# ToolDoorController.net
KiCad netlist of a schematic drawn in Altium Designer
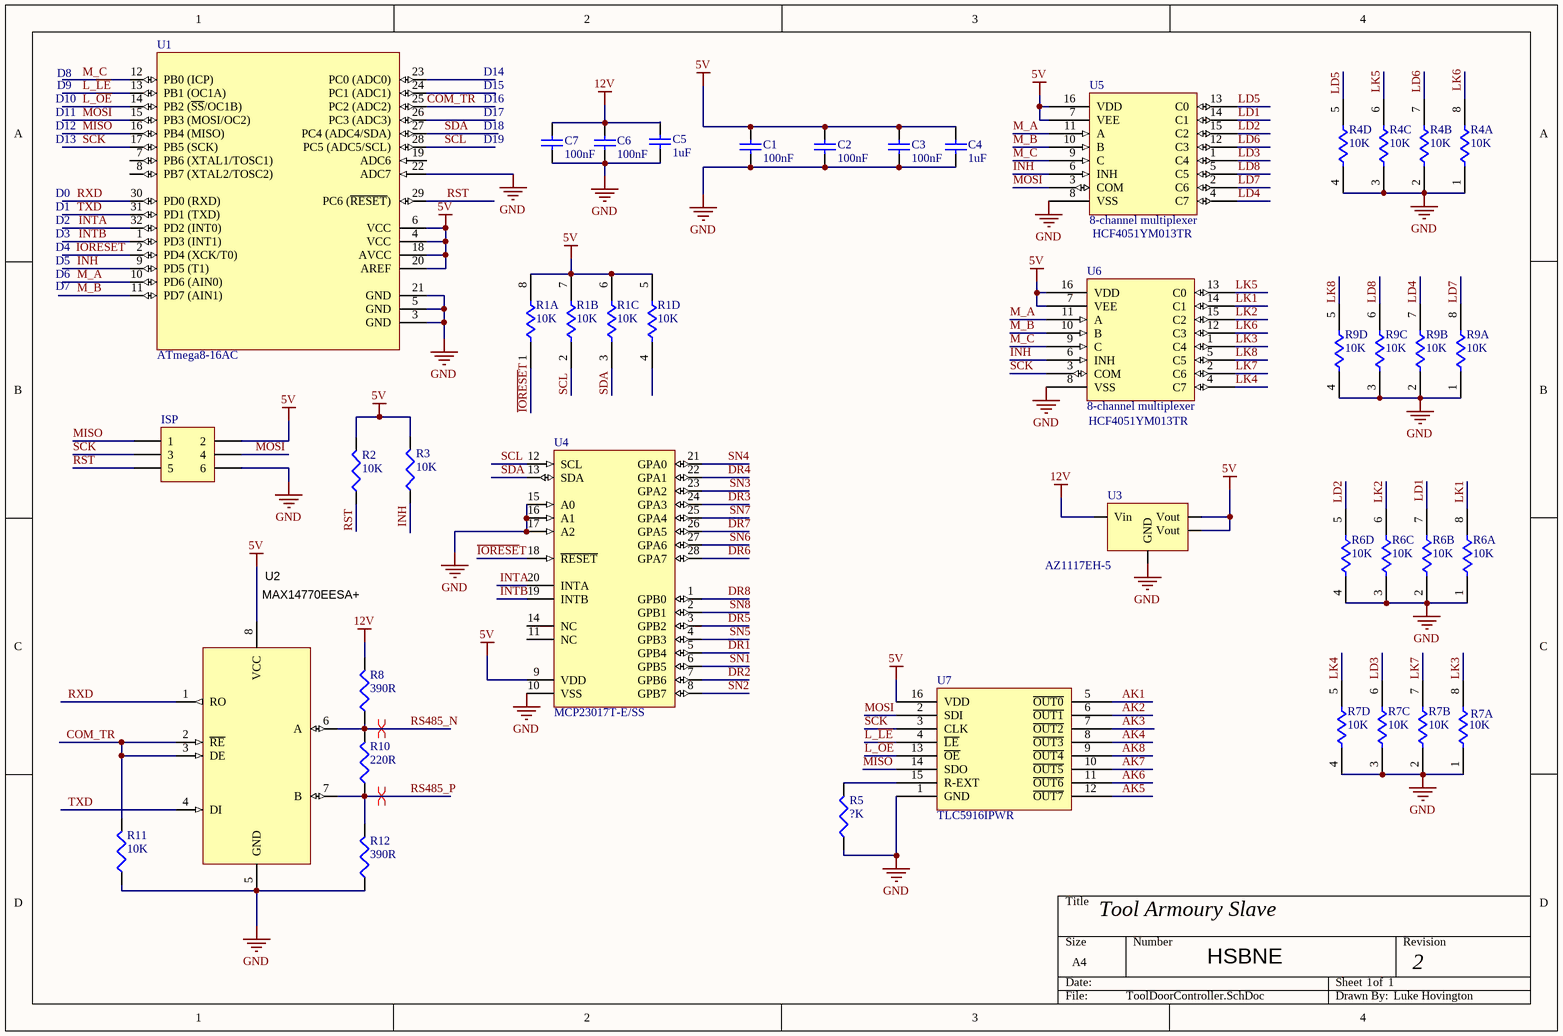
[diagram p0: ToolDoorController.SchDoc]

(export (version "E")
  (design (tool "Eeschema 10.0.6"))
  (components
    (comp (ref "C1")
      (value "100nF")
      (footprint "C1206")
      (description "Capacitor (Semiconductor SIM Model)")
      (fields (field (name "PUBLISHER") "Altium Limited"))
      (libsource (lib "ToolDoorController") (part "Cap 100nF"))
    )
    (comp (ref "C2")
      (value "100nF")
      (footprint "C1206")
      (description "Capacitor (Semiconductor SIM Model)")
      (fields (field (name "PUBLISHER") "Altium Limited"))
      (libsource (lib "ToolDoorController") (part "Cap 100nF"))
    )
    (comp (ref "C3")
      (value "100nF")
      (footprint "C1206")
      (description "Capacitor (Semiconductor SIM Model)")
      (fields (field (name "PUBLISHER") "Altium Limited"))
      (libsource (lib "ToolDoorController") (part "Cap 100nF"))
    )
    (comp (ref "C4")
      (value "1uF")
      (footprint "C1206")
      (description "Capacitor (Semiconductor SIM Model)")
      (fields (field (name "PUBLISHER") "Altium Limited"))
      (libsource (lib "ToolDoorController") (part "Cap 1uF"))
    )
    (comp (ref "C5")
      (value "1uF")
      (footprint "C1206")
      (description "Capacitor (Semiconductor SIM Model)")
      (fields (field (name "PUBLISHER") "Altium Limited"))
      (libsource (lib "ToolDoorController") (part "Cap 1uF"))
    )
    (comp (ref "C6")
      (value "100nF")
      (footprint "C1206")
      (description "Capacitor (Semiconductor SIM Model)")
      (fields (field (name "PUBLISHER") "Altium Limited"))
      (libsource (lib "ToolDoorController") (part "Cap 100nF"))
    )
    (comp (ref "C7")
      (value "100nF")
      (footprint "C1206")
      (description "Capacitor (Semiconductor SIM Model)")
      (fields (field (name "PUBLISHER") "Altium Limited"))
      (libsource (lib "ToolDoorController") (part "Cap 100nF"))
    )
    (comp (ref "ISP")
      (value "ISP")
      (footprint "HDR2X3")
      (description "Header, 3-Pin, Dual row")
      (fields (field (name "PUBLISHER") "Altium Limited"))
      (libsource (lib "ToolDoorController") (part "Header 3X2"))
    )
    (comp (ref "R1")
      (value "10K")
      (footprint "SO8_S")
      (description "Isolated Resistor Network - Parts")
      (fields (field (name "PUBLISHER") "Altium Limited"))
      (libsource (lib "ToolDoorController") (part "Resistor Pack"))
    )
    (comp (ref "R2")
      (value "10K")
      (footprint "C1206")
      (description "Resistor")
      (fields (field (name "PUBLISHER") "Altium Limited"))
      (libsource (lib "ToolDoorController") (part "Resistor-10K"))
    )
    (comp (ref "R3")
      (value "10K")
      (footprint "C1206")
      (description "Resistor")
      (fields (field (name "PUBLISHER") "Altium Limited"))
      (libsource (lib "ToolDoorController") (part "Resistor-10K"))
    )
    (comp (ref "R4")
      (value "10K")
      (footprint "SO8_S")
      (description "Isolated Resistor Network - Parts")
      (fields (field (name "PUBLISHER") "Altium Limited"))
      (libsource (lib "ToolDoorController") (part "Resistor Pack"))
    )
    (comp (ref "R5")
      (value "?K")
      (footprint "C1206")
      (description "Resistor")
      (fields (field (name "PUBLISHER") "Altium Limited"))
      (libsource (lib "ToolDoorController") (part "Resistor-10K"))
    )
    (comp (ref "R6")
      (value "10K")
      (footprint "SO8_S")
      (description "Isolated Resistor Network - Parts")
      (fields (field (name "PUBLISHER") "Altium Limited"))
      (libsource (lib "ToolDoorController") (part "Resistor Pack"))
    )
    (comp (ref "R7")
      (value "10K")
      (footprint "SO8_S")
      (description "Isolated Resistor Network - Parts")
      (fields (field (name "PUBLISHER") "Altium Limited"))
      (libsource (lib "ToolDoorController") (part "Resistor Pack"))
    )
    (comp (ref "R8")
      (value "390R")
      (footprint "C1206")
      (description "Resistor")
      (fields (field (name "PUBLISHER") "Altium Limited"))
      (libsource (lib "ToolDoorController") (part "Resistor-390R"))
    )
    (comp (ref "R9")
      (value "10K")
      (footprint "SO8_S")
      (description "Isolated Resistor Network - Parts")
      (fields (field (name "PUBLISHER") "Altium Limited"))
      (libsource (lib "ToolDoorController") (part "Resistor Pack"))
    )
    (comp (ref "R10")
      (value "220R")
      (footprint "C1206")
      (description "Resistor")
      (fields (field (name "PUBLISHER") "Altium Limited"))
      (libsource (lib "ToolDoorController") (part "Resistor-220R"))
    )
    (comp (ref "R11")
      (value "10K")
      (footprint "C1206")
      (description "Resistor")
      (fields (field (name "PUBLISHER") "Altium Limited"))
      (libsource (lib "ToolDoorController") (part "Resistor-10K"))
    )
    (comp (ref "R12")
      (value "390R")
      (footprint "C1206")
      (description "Resistor")
      (fields (field (name "PUBLISHER") "Altium Limited"))
      (libsource (lib "ToolDoorController") (part "Resistor-390R"))
    )
    (comp (ref "U1")
      (value "ATmega8-16AC")
      (footprint "32A_N")
      (description "8-Bit AVR Microcontroller with 8K Bytes of In-System Programmable Flash Memory")
      (fields (field (name "PUBLISHER") "Altium Limited"))
      (libsource (lib "ToolDoorController") (part "ATmega8-16AC"))
    )
    (comp (ref "U2")
      (value "MAX14770EESA+")
      (footprint "8S1_L")
      (description "TXRX PROFIBUS RS-485 8-SOIC")
      (libsource (lib "ToolDoorController") (part "MAX14770EESA+"))
    )
    (comp (ref "U3")
      (value "AZ1117EH-5")
      (footprint "SOT-223")
      (description "Reg 1A 5V OUT SIP VERT")
      (libsource (lib "ToolDoorController") (part "AZ1117EH"))
    )
    (comp (ref "U4")
      (value "MCP23017T-E/SS")
      (footprint "SSOP-SS28_N")
      (description "16-Bit I/O Expander with Serial Interface, 28-Pin SSOP, Extended Temperature, Tape and Reel")
      (libsource (lib "Altium Content Vault") (part "PR-BUSIC-MCP23017-28"))
    )
    (comp (ref "U5")
      (value "8-channel multiplexer")
      (footprint "16S1_M")
      (description "8-channel analog multiplexer/demultiplexer")
      (fields (field (name "MANUFACTURER PART NUMBER") "HCF4051YM013TR"))
      (libsource (lib "ToolDoorController") (part "8-channel multiplexer"))
    )
    (comp (ref "U6")
      (value "8-channel multiplexer")
      (footprint "16S1_M")
      (description "8-channel analog multiplexer/demultiplexer")
      (fields (field (name "MANUFACTURER PART NUMBER") "HCF4051YM013TR"))
      (libsource (lib "ToolDoorController") (part "8-channel multiplexer"))
    )
    (comp (ref "U7")
      (value "TLC5916IPWR")
      (footprint "DB016")
      (description "IC LED DRIVER LIN 120MA")
      (libsource (lib "ToolDoorController") (part "TLC5916IDR"))
    )
  )
  (nets
    (net (code "1") (name "/AK1") (class "Default")
      (node (ref "U7") (pin "5") (pinfunction "~{OUT0}_5") (pintype "power_in"))
    )
    (net (code "2") (name "/AK2") (class "Default")
      (node (ref "U7") (pin "6") (pinfunction "~{OUT1}_6") (pintype "power_in"))
    )
    (net (code "3") (name "/AK3") (class "Default")
      (node (ref "U7") (pin "7") (pinfunction "~{OUT2}_7") (pintype "power_in"))
    )
    (net (code "4") (name "/AK4") (class "Default")
      (node (ref "U7") (pin "8") (pinfunction "~{OUT3}_8") (pintype "power_in"))
    )
    (net (code "5") (name "/AK5") (class "Default")
      (node (ref "U7") (pin "12") (pinfunction "~{OUT7}_12") (pintype "power_in"))
    )
    (net (code "6") (name "/AK6") (class "Default")
      (node (ref "U7") (pin "11") (pinfunction "~{OUT6}_11") (pintype "power_in"))
    )
    (net (code "7") (name "/AK7") (class "Default")
      (node (ref "U7") (pin "10") (pinfunction "~{OUT5}_10") (pintype "power_in"))
    )
    (net (code "8") (name "/AK8") (class "Default")
      (node (ref "U7") (pin "9") (pinfunction "~{OUT4}_9") (pintype "power_in"))
    )
    (net (code "9") (name "/COM_TR") (class "Default")
      (node (ref "R11") (pin "2") (pinfunction "2_2") (pintype "passive"))
      (node (ref "U1") (pin "25") (pinfunction "PC2_(ADC2)_25") (pintype "bidirectional"))
      (node (ref "U2") (pin "2") (pinfunction "~{RE}_2") (pintype "input"))
      (node (ref "U2") (pin "3") (pinfunction "DE_3") (pintype "input"))
    )
    (net (code "10") (name "/DR1") (class "Default")
      (node (ref "U4") (pin "5") (pinfunction "GPB4_5") (pintype "bidirectional"))
    )
    (net (code "11") (name "/DR2") (class "Default")
      (node (ref "U4") (pin "7") (pinfunction "GPB6_7") (pintype "bidirectional"))
    )
    (net (code "12") (name "/DR3") (class "Default")
      (node (ref "U4") (pin "24") (pinfunction "GPA3_24") (pintype "bidirectional"))
    )
    (net (code "13") (name "/DR4") (class "Default")
      (node (ref "U4") (pin "22") (pinfunction "GPA1_22") (pintype "bidirectional"))
    )
    (net (code "14") (name "/DR5") (class "Default")
      (node (ref "U4") (pin "3") (pinfunction "GPB2_3") (pintype "bidirectional"))
    )
    (net (code "15") (name "/DR6") (class "Default")
      (node (ref "U4") (pin "28") (pinfunction "GPA7_28") (pintype "bidirectional"))
    )
    (net (code "16") (name "/DR7") (class "Default")
      (node (ref "U4") (pin "26") (pinfunction "GPA5_26") (pintype "bidirectional"))
    )
    (net (code "17") (name "/DR8") (class "Default")
      (node (ref "U4") (pin "1") (pinfunction "GPB0_1") (pintype "bidirectional"))
    )
    (net (code "18") (name "/INH") (class "Default")
      (node (ref "R3") (pin "1") (pinfunction "1_1") (pintype "passive"))
      (node (ref "U1") (pin "9") (pinfunction "PD5_(T1)_9") (pintype "bidirectional"))
      (node (ref "U5") (pin "6") (pinfunction "INH_6") (pintype "input"))
      (node (ref "U6") (pin "6") (pinfunction "INH_6") (pintype "input"))
    )
    (net (code "19") (name "/INTA") (class "Default")
      (node (ref "U1") (pin "32") (pinfunction "PD2_(INT0)_32") (pintype "bidirectional"))
      (node (ref "U4") (pin "20") (pinfunction "INTA_20") (pintype "open_collector"))
    )
    (net (code "20") (name "/INTB") (class "Default")
      (node (ref "U1") (pin "1") (pinfunction "PD3_(INT1)_1") (pintype "bidirectional"))
      (node (ref "U4") (pin "19") (pinfunction "INTB_19") (pintype "open_collector"))
    )
    (net (code "21") (name "/LD1") (class "Default")
      (node (ref "R6") (pin "7") (pinfunction "7_7") (pintype "passive"))
      (node (ref "U5") (pin "14") (pinfunction "C1_14") (pintype "bidirectional"))
    )
    (net (code "22") (name "/LD2") (class "Default")
      (node (ref "R6") (pin "5") (pinfunction "5_5") (pintype "passive"))
      (node (ref "U5") (pin "15") (pinfunction "C2_15") (pintype "bidirectional"))
    )
    (net (code "23") (name "/LD3") (class "Default")
      (node (ref "R7") (pin "6") (pinfunction "6_6") (pintype "passive"))
      (node (ref "U5") (pin "1") (pinfunction "C4_1") (pintype "bidirectional"))
    )
    (net (code "24") (name "/LD4") (class "Default")
      (node (ref "R9") (pin "7") (pinfunction "7_7") (pintype "passive"))
      (node (ref "U5") (pin "4") (pinfunction "C7_4") (pintype "bidirectional"))
    )
    (net (code "25") (name "/LD5") (class "Default")
      (node (ref "R4") (pin "5") (pinfunction "5_5") (pintype "passive"))
      (node (ref "U5") (pin "13") (pinfunction "C0_13") (pintype "bidirectional"))
    )
    (net (code "26") (name "/LD6") (class "Default")
      (node (ref "R4") (pin "7") (pinfunction "7_7") (pintype "passive"))
      (node (ref "U5") (pin "12") (pinfunction "C3_12") (pintype "bidirectional"))
    )
    (net (code "27") (name "/LD7") (class "Default")
      (node (ref "R9") (pin "8") (pinfunction "8_8") (pintype "passive"))
      (node (ref "U5") (pin "2") (pinfunction "C6_2") (pintype "bidirectional"))
    )
    (net (code "28") (name "/LD8") (class "Default")
      (node (ref "R9") (pin "6") (pinfunction "6_6") (pintype "passive"))
      (node (ref "U5") (pin "5") (pinfunction "C5_5") (pintype "bidirectional"))
    )
    (net (code "29") (name "/LK1") (class "Default")
      (node (ref "R6") (pin "8") (pinfunction "8_8") (pintype "passive"))
      (node (ref "U6") (pin "14") (pinfunction "C1_14") (pintype "bidirectional"))
    )
    (net (code "30") (name "/LK2") (class "Default")
      (node (ref "R6") (pin "6") (pinfunction "6_6") (pintype "passive"))
      (node (ref "U6") (pin "15") (pinfunction "C2_15") (pintype "bidirectional"))
    )
    (net (code "31") (name "/LK3") (class "Default")
      (node (ref "R7") (pin "8") (pinfunction "8_8") (pintype "passive"))
      (node (ref "U6") (pin "1") (pinfunction "C4_1") (pintype "bidirectional"))
    )
    (net (code "32") (name "/LK4") (class "Default")
      (node (ref "R7") (pin "5") (pinfunction "5_5") (pintype "passive"))
      (node (ref "U6") (pin "4") (pinfunction "C7_4") (pintype "bidirectional"))
    )
    (net (code "33") (name "/LK5") (class "Default")
      (node (ref "R4") (pin "6") (pinfunction "6_6") (pintype "passive"))
      (node (ref "U6") (pin "13") (pinfunction "C0_13") (pintype "bidirectional"))
    )
    (net (code "34") (name "/LK6") (class "Default")
      (node (ref "R4") (pin "8") (pinfunction "8_8") (pintype "passive"))
      (node (ref "U6") (pin "12") (pinfunction "C3_12") (pintype "bidirectional"))
    )
    (net (code "35") (name "/LK7") (class "Default")
      (node (ref "R7") (pin "7") (pinfunction "7_7") (pintype "passive"))
      (node (ref "U6") (pin "2") (pinfunction "C6_2") (pintype "bidirectional"))
    )
    (net (code "36") (name "/LK8") (class "Default")
      (node (ref "R9") (pin "5") (pinfunction "5_5") (pintype "passive"))
      (node (ref "U6") (pin "5") (pinfunction "C5_5") (pintype "bidirectional"))
    )
    (net (code "37") (name "/L_~{LE}") (class "Default")
      (node (ref "U1") (pin "13") (pinfunction "PB1_(OC1A)_13") (pintype "bidirectional"))
      (node (ref "U7") (pin "4") (pinfunction "~{LE}_4") (pintype "power_in"))
    )
    (net (code "38") (name "/L_~{OE}") (class "Default")
      (node (ref "U1") (pin "14") (pinfunction "PB2_(~{SS}/OC1B)_14") (pintype "bidirectional"))
      (node (ref "U7") (pin "13") (pinfunction "~{OE}_13") (pintype "power_in"))
    )
    (net (code "39") (name "/MISO") (class "Default")
      (node (ref "ISP") (pin "1") (pinfunction "1_1") (pintype "passive"))
      (node (ref "U1") (pin "16") (pinfunction "PB4_(MISO)_16") (pintype "bidirectional"))
      (node (ref "U7") (pin "14") (pinfunction "SDO_14") (pintype "power_in"))
    )
    (net (code "40") (name "/MOSI") (class "Default")
      (node (ref "ISP") (pin "4") (pinfunction "4_4") (pintype "passive"))
      (node (ref "U1") (pin "15") (pinfunction "PB3_(MOSI/OC2)_15") (pintype "bidirectional"))
      (node (ref "U5") (pin "3") (pinfunction "COM_3") (pintype "bidirectional"))
      (node (ref "U7") (pin "2") (pinfunction "SDI_2") (pintype "power_in"))
    )
    (net (code "41") (name "/M_A") (class "Default")
      (node (ref "U1") (pin "10") (pinfunction "PD6_(AIN0)_10") (pintype "bidirectional"))
      (node (ref "U5") (pin "11") (pinfunction "A_11") (pintype "input"))
      (node (ref "U6") (pin "11") (pinfunction "A_11") (pintype "input"))
    )
    (net (code "42") (name "/M_B") (class "Default")
      (node (ref "U1") (pin "11") (pinfunction "PD7_(AIN1)_11") (pintype "bidirectional"))
      (node (ref "U5") (pin "10") (pinfunction "B_10") (pintype "input"))
      (node (ref "U6") (pin "10") (pinfunction "B_10") (pintype "input"))
    )
    (net (code "43") (name "/M_C") (class "Default")
      (node (ref "U1") (pin "12") (pinfunction "PB0_(ICP)_12") (pintype "bidirectional"))
      (node (ref "U5") (pin "9") (pinfunction "C_9") (pintype "input"))
      (node (ref "U6") (pin "9") (pinfunction "C_9") (pintype "input"))
    )
    (net (code "44") (name "/RS485_N") (class "Default")
      (node (ref "R10") (pin "2") (pinfunction "2_2") (pintype "passive"))
      (node (ref "R8") (pin "1") (pinfunction "1_1") (pintype "passive"))
      (node (ref "U2") (pin "6") (pinfunction "A_6") (pintype "bidirectional"))
    )
    (net (code "45") (name "/RS485_P") (class "Default")
      (node (ref "R10") (pin "1") (pinfunction "1_1") (pintype "passive"))
      (node (ref "R12") (pin "2") (pinfunction "2_2") (pintype "passive"))
      (node (ref "U2") (pin "7") (pinfunction "B_7") (pintype "bidirectional"))
    )
    (net (code "46") (name "/RST") (class "Default")
      (node (ref "ISP") (pin "5") (pinfunction "5_5") (pintype "passive"))
      (node (ref "R2") (pin "1") (pinfunction "1_1") (pintype "passive"))
      (node (ref "U1") (pin "29") (pinfunction "PC6_(~{RESET})_29") (pintype "bidirectional"))
    )
    (net (code "47") (name "/RXD") (class "Default")
      (node (ref "U1") (pin "30") (pinfunction "PD0_(RXD)_30") (pintype "bidirectional"))
      (node (ref "U2") (pin "1") (pinfunction "RO_1") (pintype "output"))
    )
    (net (code "48") (name "/SCK") (class "Default")
      (node (ref "ISP") (pin "3") (pinfunction "3_3") (pintype "passive"))
      (node (ref "U1") (pin "17") (pinfunction "PB5_(SCK)_17") (pintype "bidirectional"))
      (node (ref "U6") (pin "3") (pinfunction "COM_3") (pintype "bidirectional"))
      (node (ref "U7") (pin "3") (pinfunction "CLK_3") (pintype "power_in"))
    )
    (net (code "49") (name "/SCL") (class "Default")
      (node (ref "R1") (pin "2") (pinfunction "2_2") (pintype "passive"))
      (node (ref "U1") (pin "28") (pinfunction "PC5_(ADC5/SCL)_28") (pintype "bidirectional"))
      (node (ref "U4") (pin "12") (pinfunction "SCL_12") (pintype "input"))
    )
    (net (code "50") (name "/SDA") (class "Default")
      (node (ref "R1") (pin "3") (pinfunction "3_3") (pintype "passive"))
      (node (ref "U1") (pin "27") (pinfunction "PC4_(ADC4/SDA)_27") (pintype "bidirectional"))
      (node (ref "U4") (pin "13") (pinfunction "SDA_13") (pintype "bidirectional"))
    )
    (net (code "51") (name "/SN1") (class "Default")
      (node (ref "U4") (pin "6") (pinfunction "GPB5_6") (pintype "bidirectional"))
    )
    (net (code "52") (name "/SN2") (class "Default")
      (node (ref "U4") (pin "8") (pinfunction "GPB7_8") (pintype "bidirectional"))
    )
    (net (code "53") (name "/SN3") (class "Default")
      (node (ref "U4") (pin "23") (pinfunction "GPA2_23") (pintype "bidirectional"))
    )
    (net (code "54") (name "/SN4") (class "Default")
      (node (ref "U4") (pin "21") (pinfunction "GPA0_21") (pintype "bidirectional"))
    )
    (net (code "55") (name "/SN5") (class "Default")
      (node (ref "U4") (pin "4") (pinfunction "GPB3_4") (pintype "bidirectional"))
    )
    (net (code "56") (name "/SN6") (class "Default")
      (node (ref "U4") (pin "27") (pinfunction "GPA6_27") (pintype "bidirectional"))
    )
    (net (code "57") (name "/SN7") (class "Default")
      (node (ref "U4") (pin "25") (pinfunction "GPA4_25") (pintype "bidirectional"))
    )
    (net (code "58") (name "/SN8") (class "Default")
      (node (ref "U4") (pin "2") (pinfunction "GPB1_2") (pintype "bidirectional"))
    )
    (net (code "59") (name "/TXD") (class "Default")
      (node (ref "U1") (pin "31") (pinfunction "PD1_(TXD)_31") (pintype "bidirectional"))
      (node (ref "U2") (pin "4") (pinfunction "DI_4") (pintype "input"))
    )
    (net (code "60") (name "/~{IORESE}T") (class "Default")
      (node (ref "R1") (pin "1") (pinfunction "1_1") (pintype "passive"))
      (node (ref "U1") (pin "2") (pinfunction "PD4_(XCK/T0)_2") (pintype "bidirectional"))
      (node (ref "U4") (pin "18") (pinfunction "~{RESET}_18") (pintype "input"))
    )
    (net (code "61") (name "5V") (class "Default")
      (node (ref "C1") (pin "2") (pinfunction "2_2") (pintype "passive"))
      (node (ref "C2") (pin "2") (pinfunction "2_2") (pintype "passive"))
      (node (ref "C3") (pin "2") (pinfunction "2_2") (pintype "passive"))
      (node (ref "C4") (pin "2") (pinfunction "2_2") (pintype "passive"))
      (node (ref "ISP") (pin "2") (pinfunction "2_2") (pintype "passive"))
      (node (ref "R1") (pin "5") (pinfunction "5_5") (pintype "passive"))
      (node (ref "R1") (pin "6") (pinfunction "6_6") (pintype "passive"))
      (node (ref "R1") (pin "7") (pinfunction "7_7") (pintype "passive"))
      (node (ref "R1") (pin "8") (pinfunction "8_8") (pintype "passive"))
      (node (ref "R2") (pin "2") (pinfunction "2_2") (pintype "passive"))
      (node (ref "R3") (pin "2") (pinfunction "2_2") (pintype "passive"))
      (node (ref "U1") (pin "18") (pinfunction "AVCC_18") (pintype "power_in"))
      (node (ref "U1") (pin "20") (pinfunction "AREF_20") (pintype "passive"))
      (node (ref "U1") (pin "4") (pinfunction "VCC_4") (pintype "power_in"))
      (node (ref "U1") (pin "6") (pinfunction "VCC_6") (pintype "power_in"))
      (node (ref "U2") (pin "8") (pinfunction "VCC_8") (pintype "power_in"))
      (node (ref "U3") (pin "2") (pinfunction "Vout_2") (pintype "power_in"))
      (node (ref "U3") (pin "4") (pinfunction "Vout_4") (pintype "power_in"))
      (node (ref "U4") (pin "9") (pinfunction "VDD_9") (pintype "power_in"))
      (node (ref "U5") (pin "16") (pinfunction "VDD_16") (pintype "power_in"))
      (node (ref "U5") (pin "7") (pinfunction "VEE_7") (pintype "power_in"))
      (node (ref "U6") (pin "16") (pinfunction "VDD_16") (pintype "power_in"))
      (node (ref "U6") (pin "7") (pinfunction "VEE_7") (pintype "power_in"))
      (node (ref "U7") (pin "16") (pinfunction "VDD_16") (pintype "power_in"))
    )
    (net (code "62") (name "12V") (class "Default")
      (node (ref "C5") (pin "2") (pinfunction "2_2") (pintype "passive"))
      (node (ref "C6") (pin "2") (pinfunction "2_2") (pintype "passive"))
      (node (ref "C7") (pin "2") (pinfunction "2_2") (pintype "passive"))
      (node (ref "R8") (pin "2") (pinfunction "2_2") (pintype "passive"))
      (node (ref "U3") (pin "3") (pinfunction "Vin_3") (pintype "power_in"))
    )
    (net (code "63") (name "GND") (class "Default")
      (node (ref "C1") (pin "1") (pinfunction "1_1") (pintype "passive"))
      (node (ref "C2") (pin "1") (pinfunction "1_1") (pintype "passive"))
      (node (ref "C3") (pin "1") (pinfunction "1_1") (pintype "passive"))
      (node (ref "C4") (pin "1") (pinfunction "1_1") (pintype "passive"))
      (node (ref "C5") (pin "1") (pinfunction "1_1") (pintype "passive"))
      (node (ref "C6") (pin "1") (pinfunction "1_1") (pintype "passive"))
      (node (ref "C7") (pin "1") (pinfunction "1_1") (pintype "passive"))
      (node (ref "ISP") (pin "6") (pinfunction "6_6") (pintype "passive"))
      (node (ref "R11") (pin "1") (pinfunction "1_1") (pintype "passive"))
      (node (ref "R12") (pin "1") (pinfunction "1_1") (pintype "passive"))
      (node (ref "R4") (pin "1") (pinfunction "1_1") (pintype "passive"))
      (node (ref "R4") (pin "2") (pinfunction "2_2") (pintype "passive"))
      (node (ref "R4") (pin "3") (pinfunction "3_3") (pintype "passive"))
      (node (ref "R4") (pin "4") (pinfunction "4_4") (pintype "passive"))
      (node (ref "R5") (pin "1") (pinfunction "1_1") (pintype "passive"))
      (node (ref "R6") (pin "1") (pinfunction "1_1") (pintype "passive"))
      (node (ref "R6") (pin "2") (pinfunction "2_2") (pintype "passive"))
      (node (ref "R6") (pin "3") (pinfunction "3_3") (pintype "passive"))
      (node (ref "R6") (pin "4") (pinfunction "4_4") (pintype "passive"))
      (node (ref "R7") (pin "1") (pinfunction "1_1") (pintype "passive"))
      (node (ref "R7") (pin "2") (pinfunction "2_2") (pintype "passive"))
      (node (ref "R7") (pin "3") (pinfunction "3_3") (pintype "passive"))
      (node (ref "R7") (pin "4") (pinfunction "4_4") (pintype "passive"))
      (node (ref "R9") (pin "1") (pinfunction "1_1") (pintype "passive"))
      (node (ref "R9") (pin "2") (pinfunction "2_2") (pintype "passive"))
      (node (ref "R9") (pin "3") (pinfunction "3_3") (pintype "passive"))
      (node (ref "R9") (pin "4") (pinfunction "4_4") (pintype "passive"))
      (node (ref "U1") (pin "21") (pinfunction "GND_21") (pintype "power_in"))
      (node (ref "U1") (pin "22") (pinfunction "ADC7_22") (pintype "input"))
      (node (ref "U1") (pin "3") (pinfunction "GND_3") (pintype "power_in"))
      (node (ref "U1") (pin "5") (pinfunction "GND_5") (pintype "power_in"))
      (node (ref "U2") (pin "5") (pinfunction "GND_5") (pintype "power_in"))
      (node (ref "U3") (pin "1") (pinfunction "GND_1") (pintype "power_in"))
      (node (ref "U4") (pin "10") (pinfunction "VSS_10") (pintype "power_in"))
      (node (ref "U4") (pin "15") (pinfunction "A0_15") (pintype "input"))
      (node (ref "U4") (pin "16") (pinfunction "A1_16") (pintype "input"))
      (node (ref "U4") (pin "17") (pinfunction "A2_17") (pintype "input"))
      (node (ref "U5") (pin "8") (pinfunction "VSS_8") (pintype "power_in"))
      (node (ref "U6") (pin "8") (pinfunction "VSS_8") (pintype "power_in"))
      (node (ref "U7") (pin "1") (pinfunction "GND_1") (pintype "power_in"))
    )
    (net (code "64") (name "Net-(U7-R-EXT)") (class "Default")
      (node (ref "R5") (pin "2") (pinfunction "2_2") (pintype "passive"))
      (node (ref "U7") (pin "15") (pinfunction "R-EXT_15") (pintype "power_in"))
    )
    (net (code "65") (name "unconnected-(R1-Pad4)") (class "Default")
      (node (ref "R1") (pin "4") (pinfunction "4_4") (pintype "passive"))
    )
    (net (code "66") (name "unconnected-(U1-ADC6-Pad19)") (class "Default")
      (node (ref "U1") (pin "19") (pinfunction "ADC6_19") (pintype "input"))
    )
    (net (code "67") (name "unconnected-(U1-PB6_(XTAL1{slash}TOSC1)-Pad7)") (class "Default")
      (node (ref "U1") (pin "7") (pinfunction "PB6_(XTAL1/TOSC1)_7") (pintype "bidirectional"))
    )
    (net (code "68") (name "unconnected-(U1-PB7_(XTAL2{slash}TOSC2)-Pad8)") (class "Default")
      (node (ref "U1") (pin "8") (pinfunction "PB7_(XTAL2/TOSC2)_8") (pintype "bidirectional"))
    )
    (net (code "69") (name "unconnected-(U1-PC0_(ADC0)-Pad23)") (class "Default")
      (node (ref "U1") (pin "23") (pinfunction "PC0_(ADC0)_23") (pintype "bidirectional"))
    )
    (net (code "70") (name "unconnected-(U1-PC1_(ADC1)-Pad24)") (class "Default")
      (node (ref "U1") (pin "24") (pinfunction "PC1_(ADC1)_24") (pintype "bidirectional"))
    )
    (net (code "71") (name "unconnected-(U1-PC3_(ADC3)-Pad26)") (class "Default")
      (node (ref "U1") (pin "26") (pinfunction "PC3_(ADC3)_26") (pintype "bidirectional"))
    )
    (net (code "72") (name "unconnected-(U4-NC-Pad11)") (class "Default")
      (node (ref "U4") (pin "11") (pinfunction "NC_11") (pintype "passive"))
    )
    (net (code "73") (name "unconnected-(U4-NC-Pad14)") (class "Default")
      (node (ref "U4") (pin "14") (pinfunction "NC_14") (pintype "passive"))
    )
  )
)
